# EddieBoardA_v2.net
KiCad netlist of a schematic drawn in EAGLE
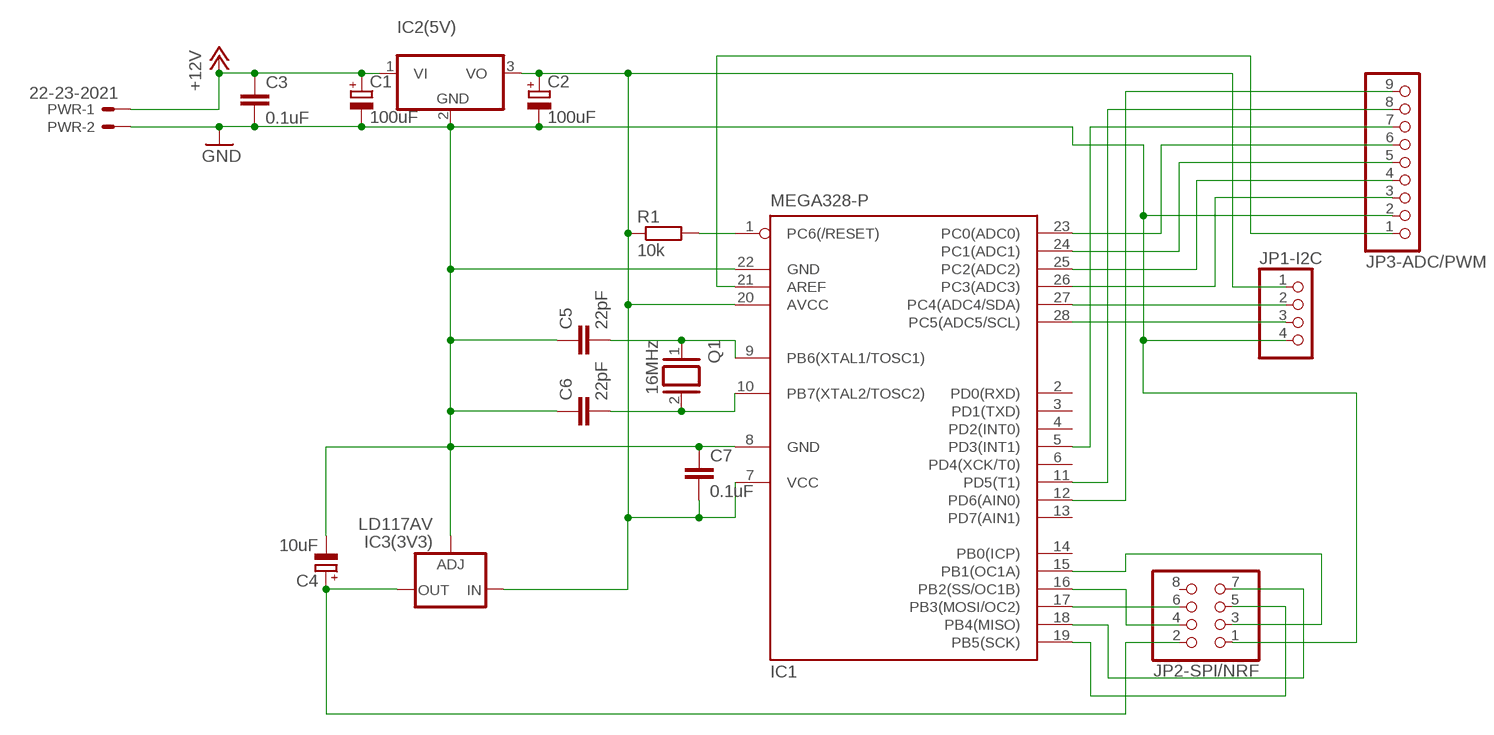
[diagram p0: schematic, sheet 1]

(export (version "E")
  (design (tool "Eeschema 10.0.6"))
  (components
    (comp (ref "C1")
      (value "100uF")
      (footprint "eagle-import:E2,5-6")
      (libsource (lib "eagle-import") (part "CPOL-EUE2.5-6"))
    )
    (comp (ref "C2")
      (value "100uF")
      (footprint "eagle-import:E2,5-6")
      (libsource (lib "eagle-import") (part "CPOL-EUE2.5-6"))
    )
    (comp (ref "C3")
      (value "0.1uF")
      (footprint "eagle-import:C025-025X050")
      (libsource (lib "eagle-import") (part "C-EU025-025X050"))
    )
    (comp (ref "C4")
      (value "10uF")
      (footprint "eagle-import:E2,5-6")
      (libsource (lib "eagle-import") (part "CPOL-EUE2.5-6"))
    )
    (comp (ref "C5")
      (value "22pF")
      (footprint "eagle-import:C025-025X050")
      (libsource (lib "eagle-import") (part "C-EU025-025X050"))
    )
    (comp (ref "C6")
      (value "22pF")
      (footprint "eagle-import:C025-025X050")
      (libsource (lib "eagle-import") (part "C-EU025-025X050"))
    )
    (comp (ref "C7")
      (value "0.1uF")
      (footprint "eagle-import:C025-025X050")
      (libsource (lib "eagle-import") (part "C-EU025-025X050"))
    )
    (comp (ref "IC1")
      (value "MEGA328-P")
      (footprint "eagle-import:DIL28-3")
      (libsource (lib "eagle-import") (part "MEGA8-P"))
    )
    (comp (ref "IC2(5V)")
      (value "7805TV")
      (footprint "eagle-import:TO220V")
      (libsource (lib "eagle-import") (part "78TV05"))
    )
    (comp (ref "IC3(3V3)")
      (value "LD117AV")
      (footprint "eagle-import:TO220L1")
      (libsource (lib "eagle-import") (part "LD117A?V"))
    )
    (comp (ref "JP1-I2C")
      (value "PINHD-1X4")
      (footprint "eagle-import:1X04")
      (libsource (lib "eagle-import") (part "PINHD-1X4"))
    )
    (comp (ref "JP2-SPI/NRF")
      (value "PINHD-2X4")
      (footprint "eagle-import:2X04")
      (libsource (lib "eagle-import") (part "PINHD-2X4"))
    )
    (comp (ref "JP3-ADC/PWM")
      (value "PINHD-1X9")
      (footprint "eagle-import:1X09")
      (libsource (lib "eagle-import") (part "PINHD-1X9"))
    )
    (comp (ref "PWR")
      (value "22-23-2021")
      (footprint "eagle-import:22-23-2021")
      (fields (field (name "MF") "MOLEX") (field (name "MPN") "PWR"))
      (libsource (lib "eagle-import") (part "22-23-2021"))
    )
    (comp (ref "Q1")
      (value "16MHz")
      (footprint "eagle-import:QS")
      (libsource (lib "eagle-import") (part "XTAL/S"))
    )
    (comp (ref "R1")
      (value "10k")
      (footprint "eagle-import:0207_12")
      (libsource (lib "eagle-import") (part "R-EU_0207/12"))
    )
  )
  (nets
    (net (code "1") (name "+12V") (class "Default")
      (node (ref "C1") (pin "+") (pinfunction "+_+") (pintype "passive"))
      (node (ref "C3") (pin "1") (pinfunction "1_1") (pintype "passive"))
      (node (ref "IC2(5V)") (pin "1") (pinfunction "VI_1") (pintype "input"))
      (node (ref "PWR") (pin "1") (pinfunction "S_1") (pintype "passive"))
    )
    (net (code "2") (name "GND") (class "Default")
      (node (ref "C1") (pin "-") (pinfunction "-_-") (pintype "passive"))
      (node (ref "C2") (pin "-") (pinfunction "-_-") (pintype "passive"))
      (node (ref "C3") (pin "2") (pinfunction "2_2") (pintype "passive"))
      (node (ref "C4") (pin "-") (pinfunction "-_-") (pintype "passive"))
      (node (ref "C5") (pin "1") (pinfunction "1_1") (pintype "passive"))
      (node (ref "C6") (pin "1") (pinfunction "1_1") (pintype "passive"))
      (node (ref "C7") (pin "1") (pinfunction "1_1") (pintype "passive"))
      (node (ref "IC1") (pin "22") (pinfunction "GND_22") (pintype "power_in"))
      (node (ref "IC1") (pin "8") (pinfunction "GND_8") (pintype "power_in"))
      (node (ref "IC2(5V)") (pin "2") (pinfunction "GND_2") (pintype "passive"))
      (node (ref "IC3(3V3)") (pin "1") (pinfunction "ADJ_1") (pintype "input"))
      (node (ref "JP1-I2C") (pin "4") (pinfunction "4_4") (pintype "passive"))
      (node (ref "JP2-SPI/NRF") (pin "1") (pinfunction "1_1") (pintype "passive"))
      (node (ref "JP3-ADC/PWM") (pin "2") (pinfunction "2_2") (pintype "passive"))
      (node (ref "PWR") (pin "2") (pinfunction "S_2") (pintype "passive"))
    )
    (net (code "3") (name "Net-(IC1-AREF)") (class "Default")
      (node (ref "IC1") (pin "21") (pinfunction "AREF_21") (pintype "passive"))
      (node (ref "JP3-ADC/PWM") (pin "1") (pinfunction "1_1") (pintype "passive"))
    )
    (net (code "4") (name "Net-(IC1-AVCC)") (class "Default")
      (node (ref "C2") (pin "+") (pinfunction "+_+") (pintype "passive"))
      (node (ref "C7") (pin "2") (pinfunction "2_2") (pintype "passive"))
      (node (ref "IC1") (pin "20") (pinfunction "AVCC_20") (pintype "power_in"))
      (node (ref "IC1") (pin "7") (pinfunction "VCC_7") (pintype "power_in"))
      (node (ref "IC2(5V)") (pin "3") (pinfunction "VO_3") (pintype "passive"))
      (node (ref "IC3(3V3)") (pin "3") (pinfunction "IN_3") (pintype "input"))
      (node (ref "JP1-I2C") (pin "1") (pinfunction "1_1") (pintype "passive"))
      (node (ref "R1") (pin "1") (pinfunction "1_1") (pintype "passive"))
    )
    (net (code "5") (name "Net-(IC1-PB1(OC1A))") (class "Default")
      (node (ref "IC1") (pin "15") (pinfunction "PB1(OC1A)_15") (pintype "bidirectional"))
      (node (ref "JP2-SPI/NRF") (pin "3") (pinfunction "3_3") (pintype "passive"))
    )
    (net (code "6") (name "Net-(IC1-PB2(SS{slash}OC1B))") (class "Default")
      (node (ref "IC1") (pin "16") (pinfunction "PB2(SS/OC1B)_16") (pintype "bidirectional"))
      (node (ref "JP2-SPI/NRF") (pin "4") (pinfunction "4_4") (pintype "passive"))
    )
    (net (code "7") (name "Net-(IC1-PB3(MOSI{slash}OC2))") (class "Default")
      (node (ref "IC1") (pin "17") (pinfunction "PB3(MOSI/OC2)_17") (pintype "bidirectional"))
      (node (ref "JP2-SPI/NRF") (pin "6") (pinfunction "6_6") (pintype "passive"))
    )
    (net (code "8") (name "Net-(IC1-PB4(MISO))") (class "Default")
      (node (ref "IC1") (pin "18") (pinfunction "PB4(MISO)_18") (pintype "bidirectional"))
      (node (ref "JP2-SPI/NRF") (pin "7") (pinfunction "7_7") (pintype "passive"))
    )
    (net (code "9") (name "Net-(IC1-PB5(SCK))") (class "Default")
      (node (ref "IC1") (pin "19") (pinfunction "PB5(SCK)_19") (pintype "bidirectional"))
      (node (ref "JP2-SPI/NRF") (pin "5") (pinfunction "5_5") (pintype "passive"))
    )
    (net (code "10") (name "Net-(IC1-PB6(XTAL1{slash}TOSC1))") (class "Default")
      (node (ref "C5") (pin "2") (pinfunction "2_2") (pintype "passive"))
      (node (ref "IC1") (pin "9") (pinfunction "PB6(XTAL1/TOSC1)_9") (pintype "bidirectional"))
      (node (ref "Q1") (pin "1") (pinfunction "1_1") (pintype "passive"))
    )
    (net (code "11") (name "Net-(IC1-PB7(XTAL2{slash}TOSC2))") (class "Default")
      (node (ref "C6") (pin "2") (pinfunction "2_2") (pintype "passive"))
      (node (ref "IC1") (pin "10") (pinfunction "PB7(XTAL2/TOSC2)_10") (pintype "bidirectional"))
      (node (ref "Q1") (pin "2") (pinfunction "2_2") (pintype "passive"))
    )
    (net (code "12") (name "Net-(IC1-PC0(ADC0))") (class "Default")
      (node (ref "IC1") (pin "23") (pinfunction "PC0(ADC0)_23") (pintype "bidirectional"))
      (node (ref "JP3-ADC/PWM") (pin "6") (pinfunction "6_6") (pintype "passive"))
    )
    (net (code "13") (name "Net-(IC1-PC1(ADC1))") (class "Default")
      (node (ref "IC1") (pin "24") (pinfunction "PC1(ADC1)_24") (pintype "bidirectional"))
      (node (ref "JP3-ADC/PWM") (pin "5") (pinfunction "5_5") (pintype "passive"))
    )
    (net (code "14") (name "Net-(IC1-PC2(ADC2))") (class "Default")
      (node (ref "IC1") (pin "25") (pinfunction "PC2(ADC2)_25") (pintype "bidirectional"))
      (node (ref "JP3-ADC/PWM") (pin "4") (pinfunction "4_4") (pintype "passive"))
    )
    (net (code "15") (name "Net-(IC1-PC3(ADC3))") (class "Default")
      (node (ref "IC1") (pin "26") (pinfunction "PC3(ADC3)_26") (pintype "bidirectional"))
      (node (ref "JP3-ADC/PWM") (pin "3") (pinfunction "3_3") (pintype "passive"))
    )
    (net (code "16") (name "Net-(IC1-PC4(ADC4{slash}SDA))") (class "Default")
      (node (ref "IC1") (pin "27") (pinfunction "PC4(ADC4/SDA)_27") (pintype "bidirectional"))
      (node (ref "JP1-I2C") (pin "2") (pinfunction "2_2") (pintype "passive"))
    )
    (net (code "17") (name "Net-(IC1-PC5(ADC5{slash}SCL))") (class "Default")
      (node (ref "IC1") (pin "28") (pinfunction "PC5(ADC5/SCL)_28") (pintype "bidirectional"))
      (node (ref "JP1-I2C") (pin "3") (pinfunction "3_3") (pintype "passive"))
    )
    (net (code "18") (name "Net-(IC1-PC6({slash}RESET))") (class "Default")
      (node (ref "IC1") (pin "1") (pinfunction "PC6(/RESET)_1") (pintype "bidirectional"))
      (node (ref "R1") (pin "2") (pinfunction "2_2") (pintype "passive"))
    )
    (net (code "19") (name "Net-(IC1-PD3(INT1))") (class "Default")
      (node (ref "IC1") (pin "5") (pinfunction "PD3(INT1)_5") (pintype "bidirectional"))
      (node (ref "JP3-ADC/PWM") (pin "7") (pinfunction "7_7") (pintype "passive"))
    )
    (net (code "20") (name "Net-(IC1-PD5(T1))") (class "Default")
      (node (ref "IC1") (pin "11") (pinfunction "PD5(T1)_11") (pintype "bidirectional"))
      (node (ref "JP3-ADC/PWM") (pin "8") (pinfunction "8_8") (pintype "passive"))
    )
    (net (code "21") (name "Net-(IC1-PD6(AIN0))") (class "Default")
      (node (ref "IC1") (pin "12") (pinfunction "PD6(AIN0)_12") (pintype "bidirectional"))
      (node (ref "JP3-ADC/PWM") (pin "9") (pinfunction "9_9") (pintype "passive"))
    )
    (net (code "22") (name "Net-(IC3(3V3)-OUT)") (class "Default")
      (node (ref "C4") (pin "+") (pinfunction "+_+") (pintype "passive"))
      (node (ref "IC3(3V3)") (pin "2") (pinfunction "OUT_2") (pintype "passive"))
      (node (ref "JP2-SPI/NRF") (pin "2") (pinfunction "2_2") (pintype "passive"))
    )
    (net (code "23") (name "unconnected-(IC1-PB0(ICP)-Pad14)") (class "Default")
      (node (ref "IC1") (pin "14") (pinfunction "PB0(ICP)_14") (pintype "bidirectional"))
    )
    (net (code "24") (name "unconnected-(IC1-PD0(RXD)-Pad2)") (class "Default")
      (node (ref "IC1") (pin "2") (pinfunction "PD0(RXD)_2") (pintype "bidirectional"))
    )
    (net (code "25") (name "unconnected-(IC1-PD1(TXD)-Pad3)") (class "Default")
      (node (ref "IC1") (pin "3") (pinfunction "PD1(TXD)_3") (pintype "bidirectional"))
    )
    (net (code "26") (name "unconnected-(IC1-PD2(INT0)-Pad4)") (class "Default")
      (node (ref "IC1") (pin "4") (pinfunction "PD2(INT0)_4") (pintype "bidirectional"))
    )
    (net (code "27") (name "unconnected-(IC1-PD4(XCK{slash}T0)-Pad6)") (class "Default")
      (node (ref "IC1") (pin "6") (pinfunction "PD4(XCK/T0)_6") (pintype "bidirectional"))
    )
    (net (code "28") (name "unconnected-(IC1-PD7(AIN1)-Pad13)") (class "Default")
      (node (ref "IC1") (pin "13") (pinfunction "PD7(AIN1)_13") (pintype "bidirectional"))
    )
    (net (code "29") (name "unconnected-(JP2-SPI/NRF-Pad8)") (class "Default")
      (node (ref "JP2-SPI/NRF") (pin "8") (pinfunction "8_8") (pintype "passive"))
    )
  )
)
